# ESP_AutoFlasher.net
KiCad netlist of a schematic drawn in Altium Designer
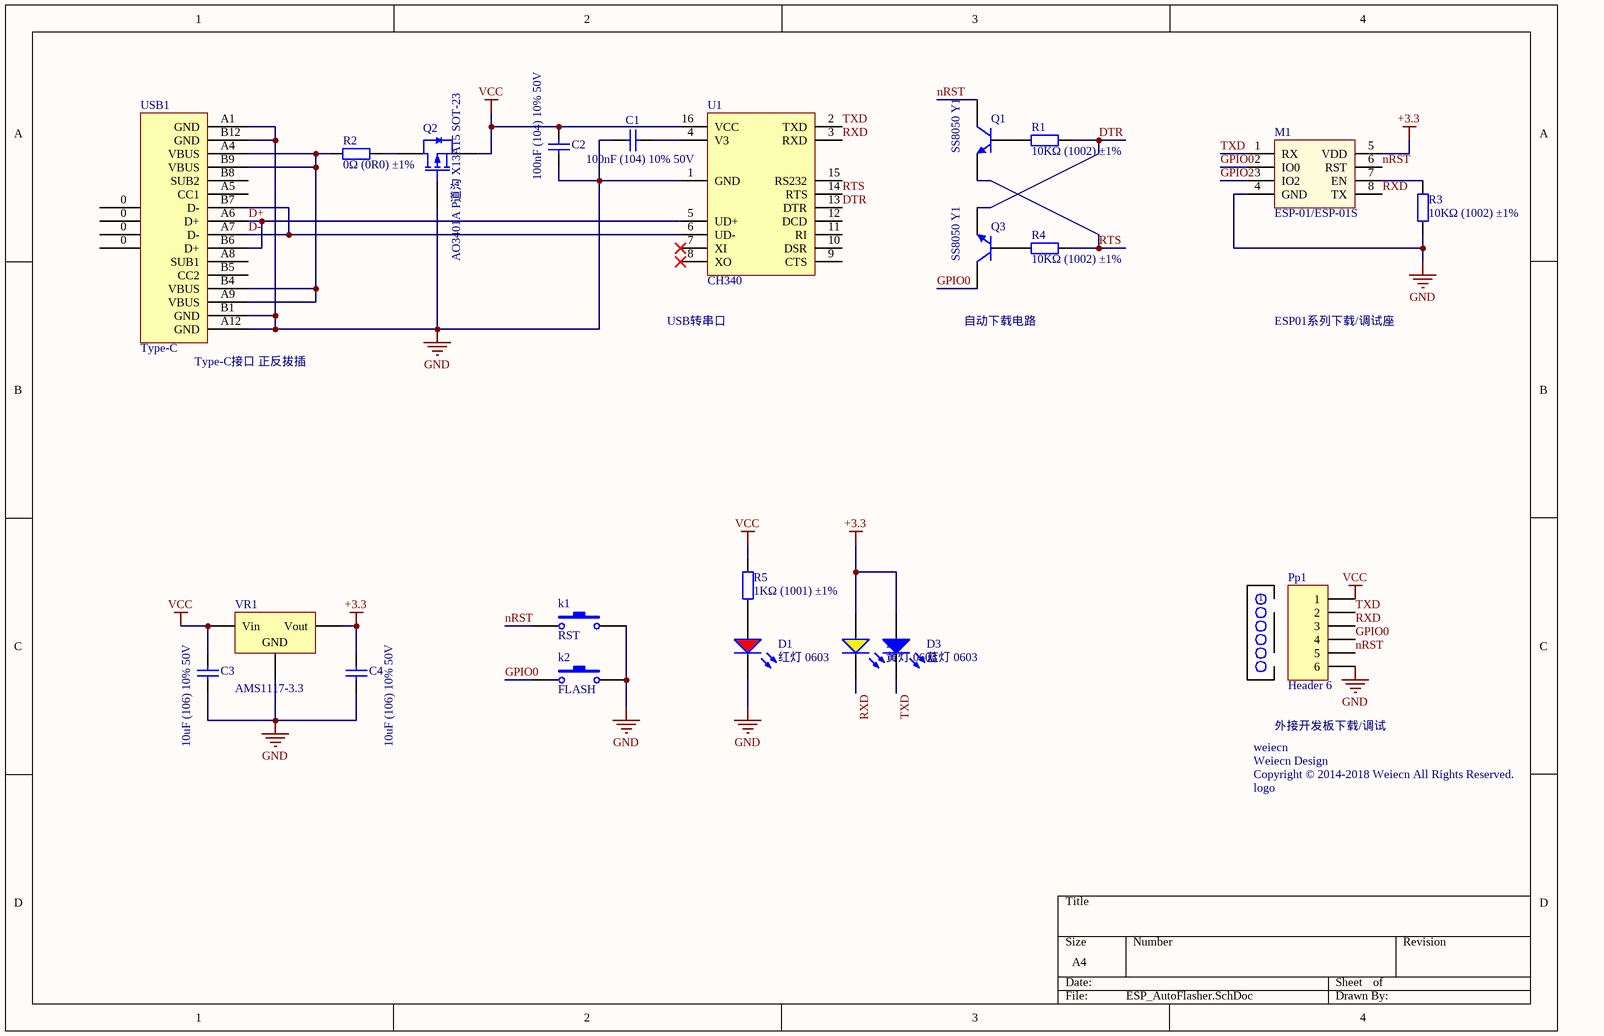
[diagram p0: ESP_AutoFlasher.SchDoc]

(export (version "E")
  (design (tool "Eeschema 10.0.6"))
  (components
    (comp (ref "C1")
      (value "100nF (104) 10% 50V")
      (footprint "0603_C")
      (description "贴片电容")
      (libsource (lib "Miscellaneous Devices LC") (part "0603 100nF (104) 10% 50V"))
    )
    (comp (ref "C2")
      (value "100nF (104) 10% 50V")
      (footprint "0603_C")
      (description "贴片电容")
      (libsource (lib "Miscellaneous Devices LC") (part "0603 100nF (104) 10% 50V"))
    )
    (comp (ref "C3")
      (value "10uF (106) 10% 50V")
      (footprint "1206_C")
      (description "贴片电容")
      (libsource (lib "Miscellaneous Devices LC") (part "1206 10uF (106) 10% 50V"))
    )
    (comp (ref "C4")
      (value "10uF (106) 10% 50V")
      (footprint "1206_C")
      (description "贴片电容")
      (libsource (lib "Miscellaneous Devices LC") (part "1206 10uF (106) 10% 50V"))
    )
    (comp (ref "D1")
      (value "红灯 0603")
      (footprint "0603_LED_S1")
      (description "发光二极管")
      (libsource (lib "Miscellaneous Devices LC") (part "0603 红灯"))
    )
    (comp (ref "D2")
      (value "黄灯 0603")
      (footprint "0603_LED_S1")
      (description "发光二极管")
      (libsource (lib "Miscellaneous Devices LC") (part "0603 黄灯"))
    )
    (comp (ref "D3")
      (value "蓝灯 0603")
      (footprint "0603_LED_S1")
      (description "发光二极管")
      (libsource (lib "Miscellaneous Devices LC") (part "0603 蓝灯"))
    )
    (comp (ref "k1")
      (value "RST")
      (footprint "SW-3*4")
      (description "按键")
      (libsource (lib "元器件库") (part "SW"))
    )
    (comp (ref "k2")
      (value "FLASH")
      (footprint "SW-3*4")
      (description "按键")
      (libsource (lib "元器件库") (part "SW"))
    )
    (comp (ref "M1")
      (value "ESP-01/ESP-01S")
      (footprint "ESP-01&01S Module")
      (description "ESP-01/ESP-01S 模块")
      (libsource (lib "元器件库") (part "ESP-01&01S Module"))
    )
    (comp (ref "Pp1")
      (value "Header 6")
      (footprint "6p")
      (description "Header, 6-Pin")
      (fields (field (name "PUBLISHER") "Altium Limited"))
      (libsource (lib "元器件库") (part "Header 6"))
    )
    (comp (ref "Q1")
      (value "SS8050 Y1")
      (footprint "SOT-23(SOT-23-3)")
      (description "三极管")
      (libsource (lib "Miscellaneous Devices LC") (part "SOT-23 SS8050 Y1"))
    )
    (comp (ref "Q2")
      (value "AO3401A P道沟 X13A15 SOT-23")
      (footprint "SOT-23-3L")
      (description "MOS(场效应管)")
      (libsource (lib "Miscellaneous Devices LC") (part "AO3401A P道沟 X13A15 SOT-23"))
    )
    (comp (ref "Q3")
      (value "SS8050 Y1")
      (footprint "SOT-23(SOT-23-3)")
      (description "三极管")
      (libsource (lib "Miscellaneous Devices LC") (part "SOT-23 SS8050 Y1"))
    )
    (comp (ref "R1")
      (value "10KΩ (1002) ±1%")
      (footprint "0603_R")
      (description "贴片电阻")
      (libsource (lib "") (part "0603 10KΩ (1002) 1%_1"))
    )
    (comp (ref "R2")
      (value "0Ω (0R0) ±1%")
      (footprint "0805_R")
      (description "贴片电阻")
      (libsource (lib "Miscellaneous Devices LC") (part "0805 0Ω (0R0) 1%"))
    )
    (comp (ref "R3")
      (value "10KΩ (1002) ±1%")
      (footprint "0603_R")
      (description "贴片电阻")
      (libsource (lib "Miscellaneous Devices LC") (part "0603 10KΩ (1002) 1%"))
    )
    (comp (ref "R4")
      (value "10KΩ (1002) ±1%")
      (footprint "0603_R")
      (description "贴片电阻")
      (libsource (lib "") (part "0603 10KΩ (1002) 1%_1"))
    )
    (comp (ref "R5")
      (value "1KΩ (1001) ±1%")
      (footprint "0603_R")
      (description "贴片电阻")
      (libsource (lib "Miscellaneous Devices LC") (part "0603 1KΩ (1001) 1%"))
    )
    (comp (ref "U1") (value "CH340") (footprint "SO_16") (libsource (lib "元器件库") (part "CH340")))
    (comp (ref "USB1")
      (value "Type-C")
      (footprint "Type-C_Socket_16P")
      (description "USB 3.1  单排16PIN四脚插板(L=7.35) 一体式MD")
      (libsource (lib "元器件库") (part "Type-C Socket"))
    )
    (comp (ref "VR1")
      (value "AMS1117-3.3")
      (footprint "SOT-223")
      (description "低压差线性稳压(LDO)")
      (libsource (lib "Miscellaneous Devices LC") (part "SOT-223 AMS1117-3.3"))
    )
    (comp (ref "weiecn") (value "logo") (footprint "Weiecn-LOGO") (libsource (lib "元器件库") (part "logo")))
  )
  (nets
    (net (code "1") (name "+3.3") (class "Default")
      (node (ref "C4") (pin "2") (pinfunction "2_2") (pintype "passive"))
      (node (ref "D2") (pin "A") (pinfunction "A_A") (pintype "passive"))
      (node (ref "D3") (pin "A") (pinfunction "A_A") (pintype "passive"))
      (node (ref "M1") (pin "5") (pinfunction "VDD_5") (pintype "passive"))
      (node (ref "VR1") (pin "2") (pinfunction "Vout_2") (pintype "passive"))
    )
    (net (code "2") (name "/D+") (class "Default")
      (node (ref "U1") (pin "5") (pinfunction "UD+_5") (pintype "passive"))
      (node (ref "USB1") (pin "A6") (pinfunction "D+_A6") (pintype "passive"))
      (node (ref "USB1") (pin "B6") (pinfunction "D+_B6") (pintype "passive"))
    )
    (net (code "3") (name "/D-") (class "Default")
      (node (ref "U1") (pin "6") (pinfunction "UD-_6") (pintype "passive"))
      (node (ref "USB1") (pin "A7") (pinfunction "D-_A7") (pintype "passive"))
      (node (ref "USB1") (pin "B7") (pinfunction "D-_B7") (pintype "passive"))
    )
    (net (code "4") (name "/DTR") (class "Default")
      (node (ref "Q3") (pin "2") (pinfunction "E_2") (pintype "passive"))
      (node (ref "R1") (pin "2") (pinfunction "2_2") (pintype "passive"))
      (node (ref "U1") (pin "13") (pinfunction "DTR_13") (pintype "passive"))
    )
    (net (code "5") (name "/GPIO0") (class "Default")
      (node (ref "M1") (pin "2") (pinfunction "IO0_2") (pintype "passive"))
      (node (ref "Pp1") (pin "4") (pinfunction "4_4") (pintype "passive"))
      (node (ref "Q3") (pin "3") (pinfunction "C_3") (pintype "passive"))
      (node (ref "k2") (pin "1") (pinfunction "1_1") (pintype "passive"))
    )
    (net (code "6") (name "/GPIO2") (class "Default")
      (node (ref "M1") (pin "3") (pinfunction "IO2_3") (pintype "passive"))
    )
    (net (code "7") (name "/RTS") (class "Default")
      (node (ref "Q1") (pin "2") (pinfunction "E_2") (pintype "passive"))
      (node (ref "R4") (pin "2") (pinfunction "2_2") (pintype "passive"))
      (node (ref "U1") (pin "14") (pinfunction "RTS_14") (pintype "passive"))
    )
    (net (code "8") (name "/RXD") (class "Default")
      (node (ref "D2") (pin "K") (pinfunction "K_K") (pintype "passive"))
      (node (ref "M1") (pin "8") (pinfunction "TX_8") (pintype "passive"))
      (node (ref "Pp1") (pin "3") (pinfunction "3_3") (pintype "passive"))
      (node (ref "U1") (pin "3") (pinfunction "RXD_3") (pintype "passive"))
    )
    (net (code "9") (name "/TXD") (class "Default")
      (node (ref "D3") (pin "K") (pinfunction "K_K") (pintype "passive"))
      (node (ref "M1") (pin "1") (pinfunction "RX_1") (pintype "passive"))
      (node (ref "Pp1") (pin "2") (pinfunction "2_2") (pintype "passive"))
      (node (ref "U1") (pin "2") (pinfunction "TXD_2") (pintype "passive"))
    )
    (net (code "10") (name "/nRST") (class "Default")
      (node (ref "M1") (pin "6") (pinfunction "RST_6") (pintype "passive"))
      (node (ref "Pp1") (pin "5") (pinfunction "5_5") (pintype "passive"))
      (node (ref "Q1") (pin "3") (pinfunction "C_3") (pintype "passive"))
      (node (ref "k1") (pin "1") (pinfunction "1_1") (pintype "passive"))
    )
    (net (code "11") (name "GND") (class "Default")
      (node (ref "C1") (pin "1") (pinfunction "1_1") (pintype "passive"))
      (node (ref "C2") (pin "1") (pinfunction "1_1") (pintype "passive"))
      (node (ref "C3") (pin "1") (pinfunction "1_1") (pintype "passive"))
      (node (ref "C4") (pin "1") (pinfunction "1_1") (pintype "passive"))
      (node (ref "D1") (pin "K") (pinfunction "K_K") (pintype "passive"))
      (node (ref "M1") (pin "4") (pinfunction "GND_4") (pintype "passive"))
      (node (ref "Pp1") (pin "6") (pinfunction "6_6") (pintype "passive"))
      (node (ref "Q2") (pin "1") (pinfunction "G_1") (pintype "passive"))
      (node (ref "R3") (pin "1") (pinfunction "1_1") (pintype "passive"))
      (node (ref "U1") (pin "1") (pinfunction "GND_1") (pintype "passive"))
      (node (ref "USB1") (pin "A1") (pinfunction "GND_A1") (pintype "passive"))
      (node (ref "USB1") (pin "A12") (pinfunction "GND_A12") (pintype "passive"))
      (node (ref "USB1") (pin "B1") (pinfunction "GND_B1") (pintype "passive"))
      (node (ref "USB1") (pin "B12") (pinfunction "GND_B12") (pintype "passive"))
      (node (ref "VR1") (pin "1") (pinfunction "GND_1") (pintype "passive"))
      (node (ref "k1") (pin "2") (pinfunction "2_2") (pintype "passive"))
      (node (ref "k2") (pin "2") (pinfunction "2_2") (pintype "passive"))
    )
    (net (code "12") (name "Net-(D1-PadA)") (class "Default")
      (node (ref "D1") (pin "A") (pinfunction "A_A") (pintype "passive"))
      (node (ref "R5") (pin "1") (pinfunction "1_1") (pintype "passive"))
    )
    (net (code "13") (name "Net-(M1-EN)") (class "Default")
      (node (ref "M1") (pin "7") (pinfunction "EN_7") (pintype "passive"))
      (node (ref "R3") (pin "2") (pinfunction "2_2") (pintype "passive"))
    )
    (net (code "14") (name "Net-(Q1-B)") (class "Default")
      (node (ref "Q1") (pin "1") (pinfunction "B_1") (pintype "passive"))
      (node (ref "R1") (pin "1") (pinfunction "1_1") (pintype "passive"))
    )
    (net (code "15") (name "Net-(Q2-D)") (class "Default")
      (node (ref "Q2") (pin "3") (pinfunction "D_3") (pintype "passive"))
      (node (ref "R2") (pin "2") (pinfunction "2_2") (pintype "passive"))
    )
    (net (code "16") (name "Net-(Q3-B)") (class "Default")
      (node (ref "Q3") (pin "1") (pinfunction "B_1") (pintype "passive"))
      (node (ref "R4") (pin "1") (pinfunction "1_1") (pintype "passive"))
    )
    (net (code "17") (name "Net-(R2-Pad1)") (class "Default")
      (node (ref "R2") (pin "1") (pinfunction "1_1") (pintype "passive"))
      (node (ref "USB1") (pin "A4") (pinfunction "VBUS_A4") (pintype "passive"))
      (node (ref "USB1") (pin "A9") (pinfunction "VBUS_A9") (pintype "passive"))
      (node (ref "USB1") (pin "B4") (pinfunction "VBUS_B4") (pintype "passive"))
      (node (ref "USB1") (pin "B9") (pinfunction "VBUS_B9") (pintype "passive"))
    )
    (net (code "18") (name "Net-(U1-V3)") (class "Default")
      (node (ref "C1") (pin "2") (pinfunction "2_2") (pintype "passive"))
      (node (ref "U1") (pin "4") (pinfunction "V3_4") (pintype "passive"))
    )
    (net (code "19") (name "VCC") (class "Default")
      (node (ref "C2") (pin "2") (pinfunction "2_2") (pintype "passive"))
      (node (ref "C3") (pin "2") (pinfunction "2_2") (pintype "passive"))
      (node (ref "Pp1") (pin "1") (pinfunction "1_1") (pintype "passive"))
      (node (ref "Q2") (pin "2") (pinfunction "S_2") (pintype "passive"))
      (node (ref "R5") (pin "2") (pinfunction "2_2") (pintype "passive"))
      (node (ref "U1") (pin "16") (pinfunction "VCC_16") (pintype "passive"))
      (node (ref "VR1") (pin "3") (pinfunction "Vin_3") (pintype "passive"))
    )
    (net (code "20") (name "unconnected-(U1-CTS-Pad9)") (class "Default")
      (node (ref "U1") (pin "9") (pinfunction "CTS_9") (pintype "passive"))
    )
    (net (code "21") (name "unconnected-(U1-DCD-Pad12)") (class "Default")
      (node (ref "U1") (pin "12") (pinfunction "DCD_12") (pintype "passive"))
    )
    (net (code "22") (name "unconnected-(U1-DSR-Pad10)") (class "Default")
      (node (ref "U1") (pin "10") (pinfunction "DSR_10") (pintype "passive"))
    )
    (net (code "23") (name "unconnected-(U1-RI-Pad11)") (class "Default")
      (node (ref "U1") (pin "11") (pinfunction "RI_11") (pintype "passive"))
    )
    (net (code "24") (name "unconnected-(U1-RS232-Pad15)") (class "Default")
      (node (ref "U1") (pin "15") (pinfunction "RS232_15") (pintype "passive"))
    )
    (net (code "25") (name "unconnected-(U1-XI-Pad7)") (class "Default")
      (node (ref "U1") (pin "7") (pinfunction "XI_7") (pintype "passive+no_connect"))
    )
    (net (code "26") (name "unconnected-(U1-XO-Pad8)") (class "Default")
      (node (ref "U1") (pin "8") (pinfunction "XO_8") (pintype "passive+no_connect"))
    )
    (net (code "27") (name "unconnected-(USB1-CC1-PadA5)") (class "Default")
      (node (ref "USB1") (pin "A5") (pinfunction "CC1_A5") (pintype "passive"))
    )
    (net (code "28") (name "unconnected-(USB1-CC2-PadB5)") (class "Default")
      (node (ref "USB1") (pin "B5") (pinfunction "CC2_B5") (pintype "passive"))
    )
    (net (code "29") (name "unconnected-(USB1-Pad0)") (class "Default")
      (node (ref "USB1") (pin "0") (pintype "passive"))
    )
    (net (code "30") (name "unconnected-(USB1-Pad0)_1") (class "Default")
      (node (ref "USB1") (pin "0") (pintype "passive"))
    )
    (net (code "31") (name "unconnected-(USB1-Pad0)_2") (class "Default")
      (node (ref "USB1") (pin "0") (pintype "passive"))
    )
    (net (code "32") (name "unconnected-(USB1-Pad0)_3") (class "Default")
      (node (ref "USB1") (pin "0") (pintype "passive"))
    )
    (net (code "33") (name "unconnected-(USB1-SUB1-PadA8)") (class "Default")
      (node (ref "USB1") (pin "A8") (pinfunction "SUB1_A8") (pintype "passive"))
    )
    (net (code "34") (name "unconnected-(USB1-SUB2-PadB8)") (class "Default")
      (node (ref "USB1") (pin "B8") (pinfunction "SUB2_B8") (pintype "passive"))
    )
  )
)
